# mysz.net
KiCad netlist of a schematic drawn in EAGLE
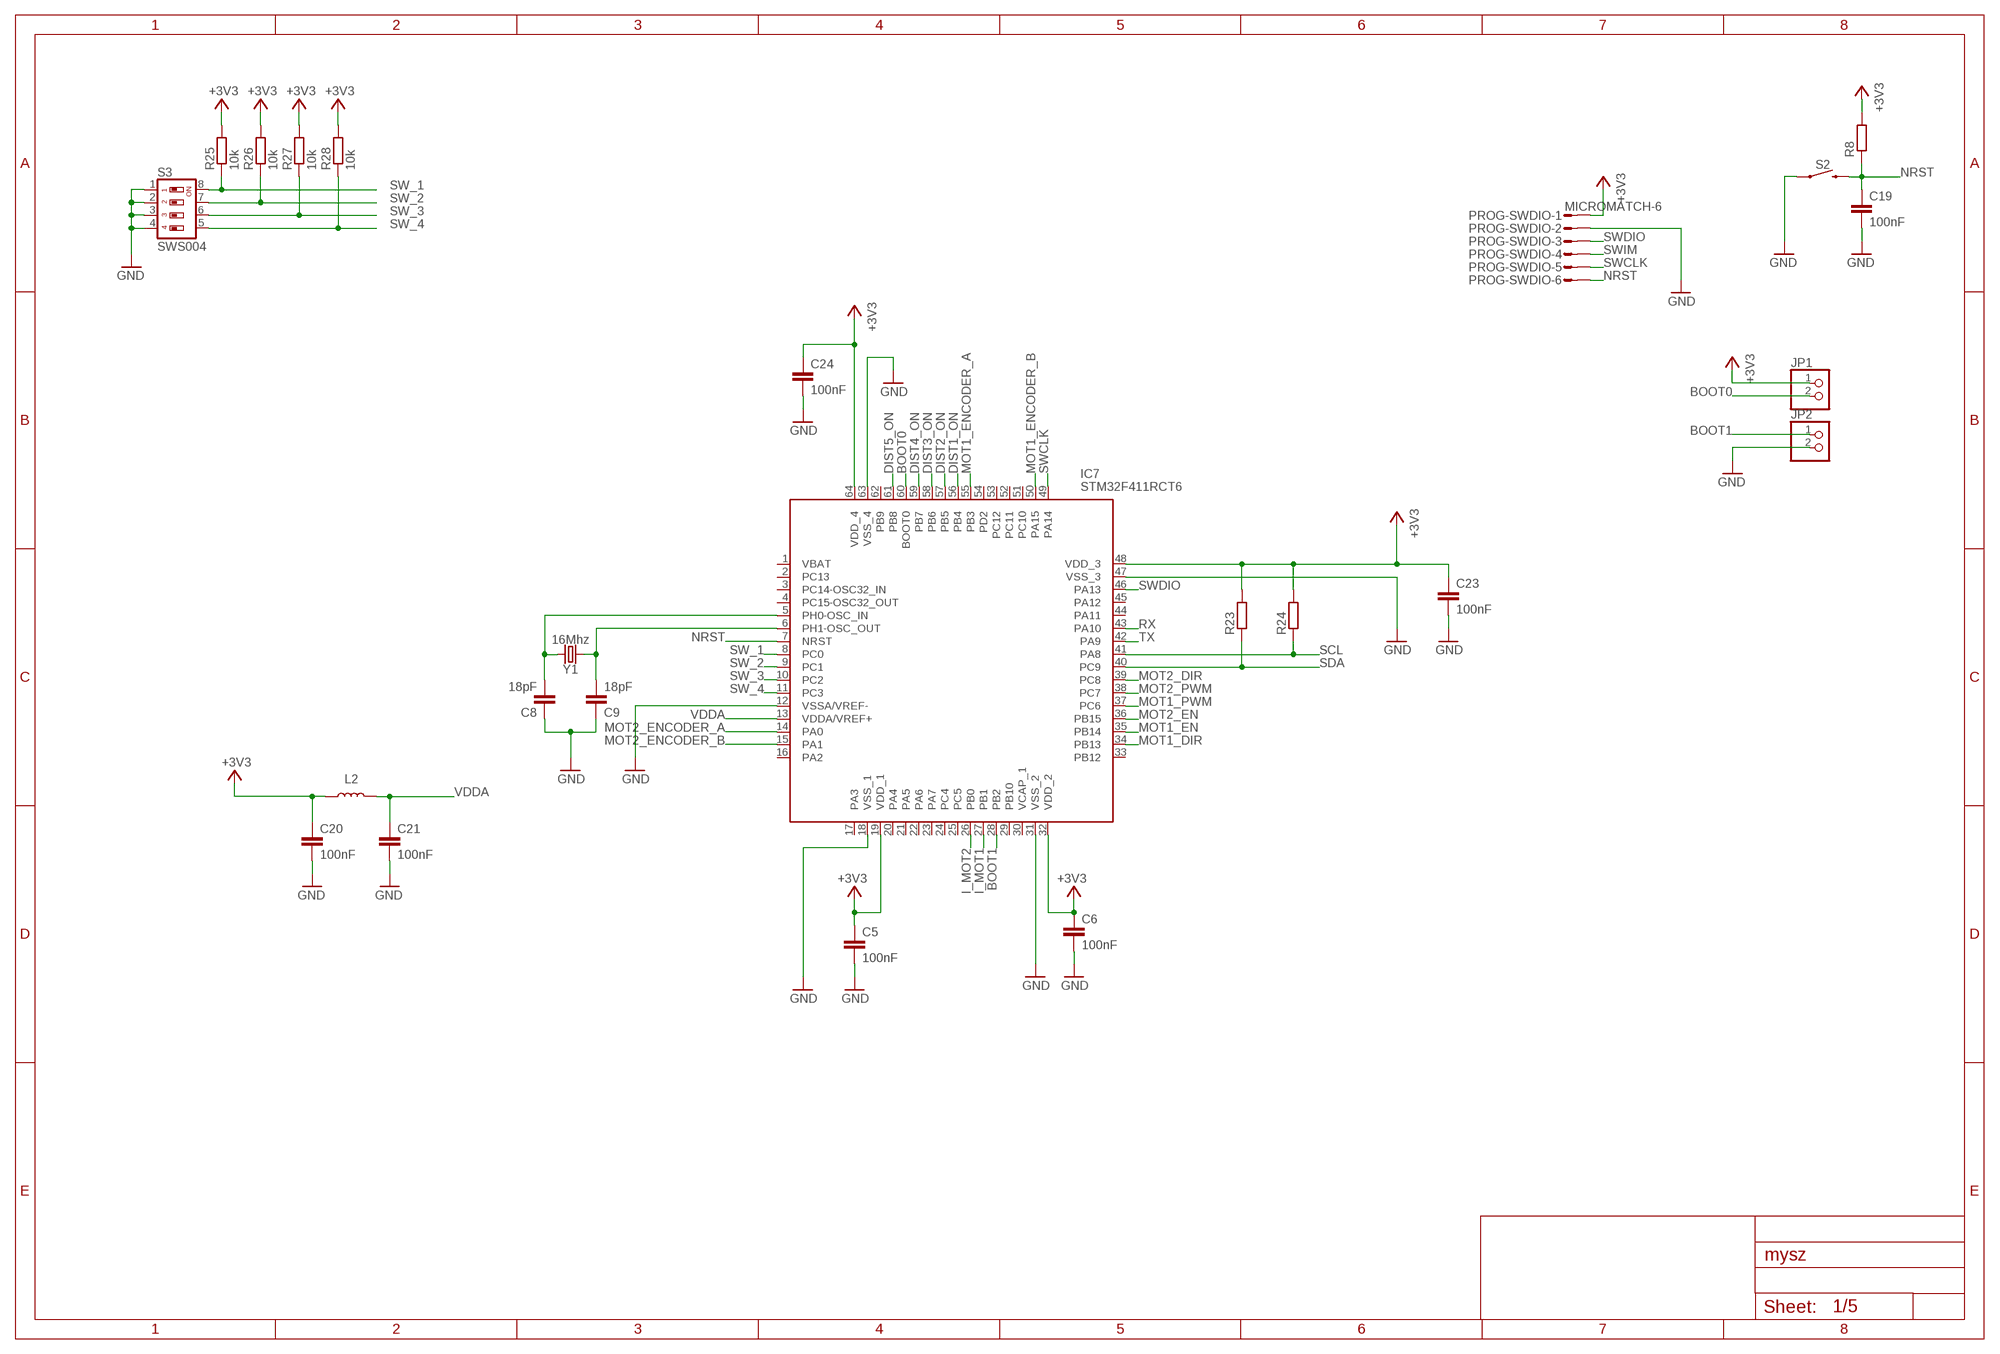
[diagram p0: schematic, sheet 1]
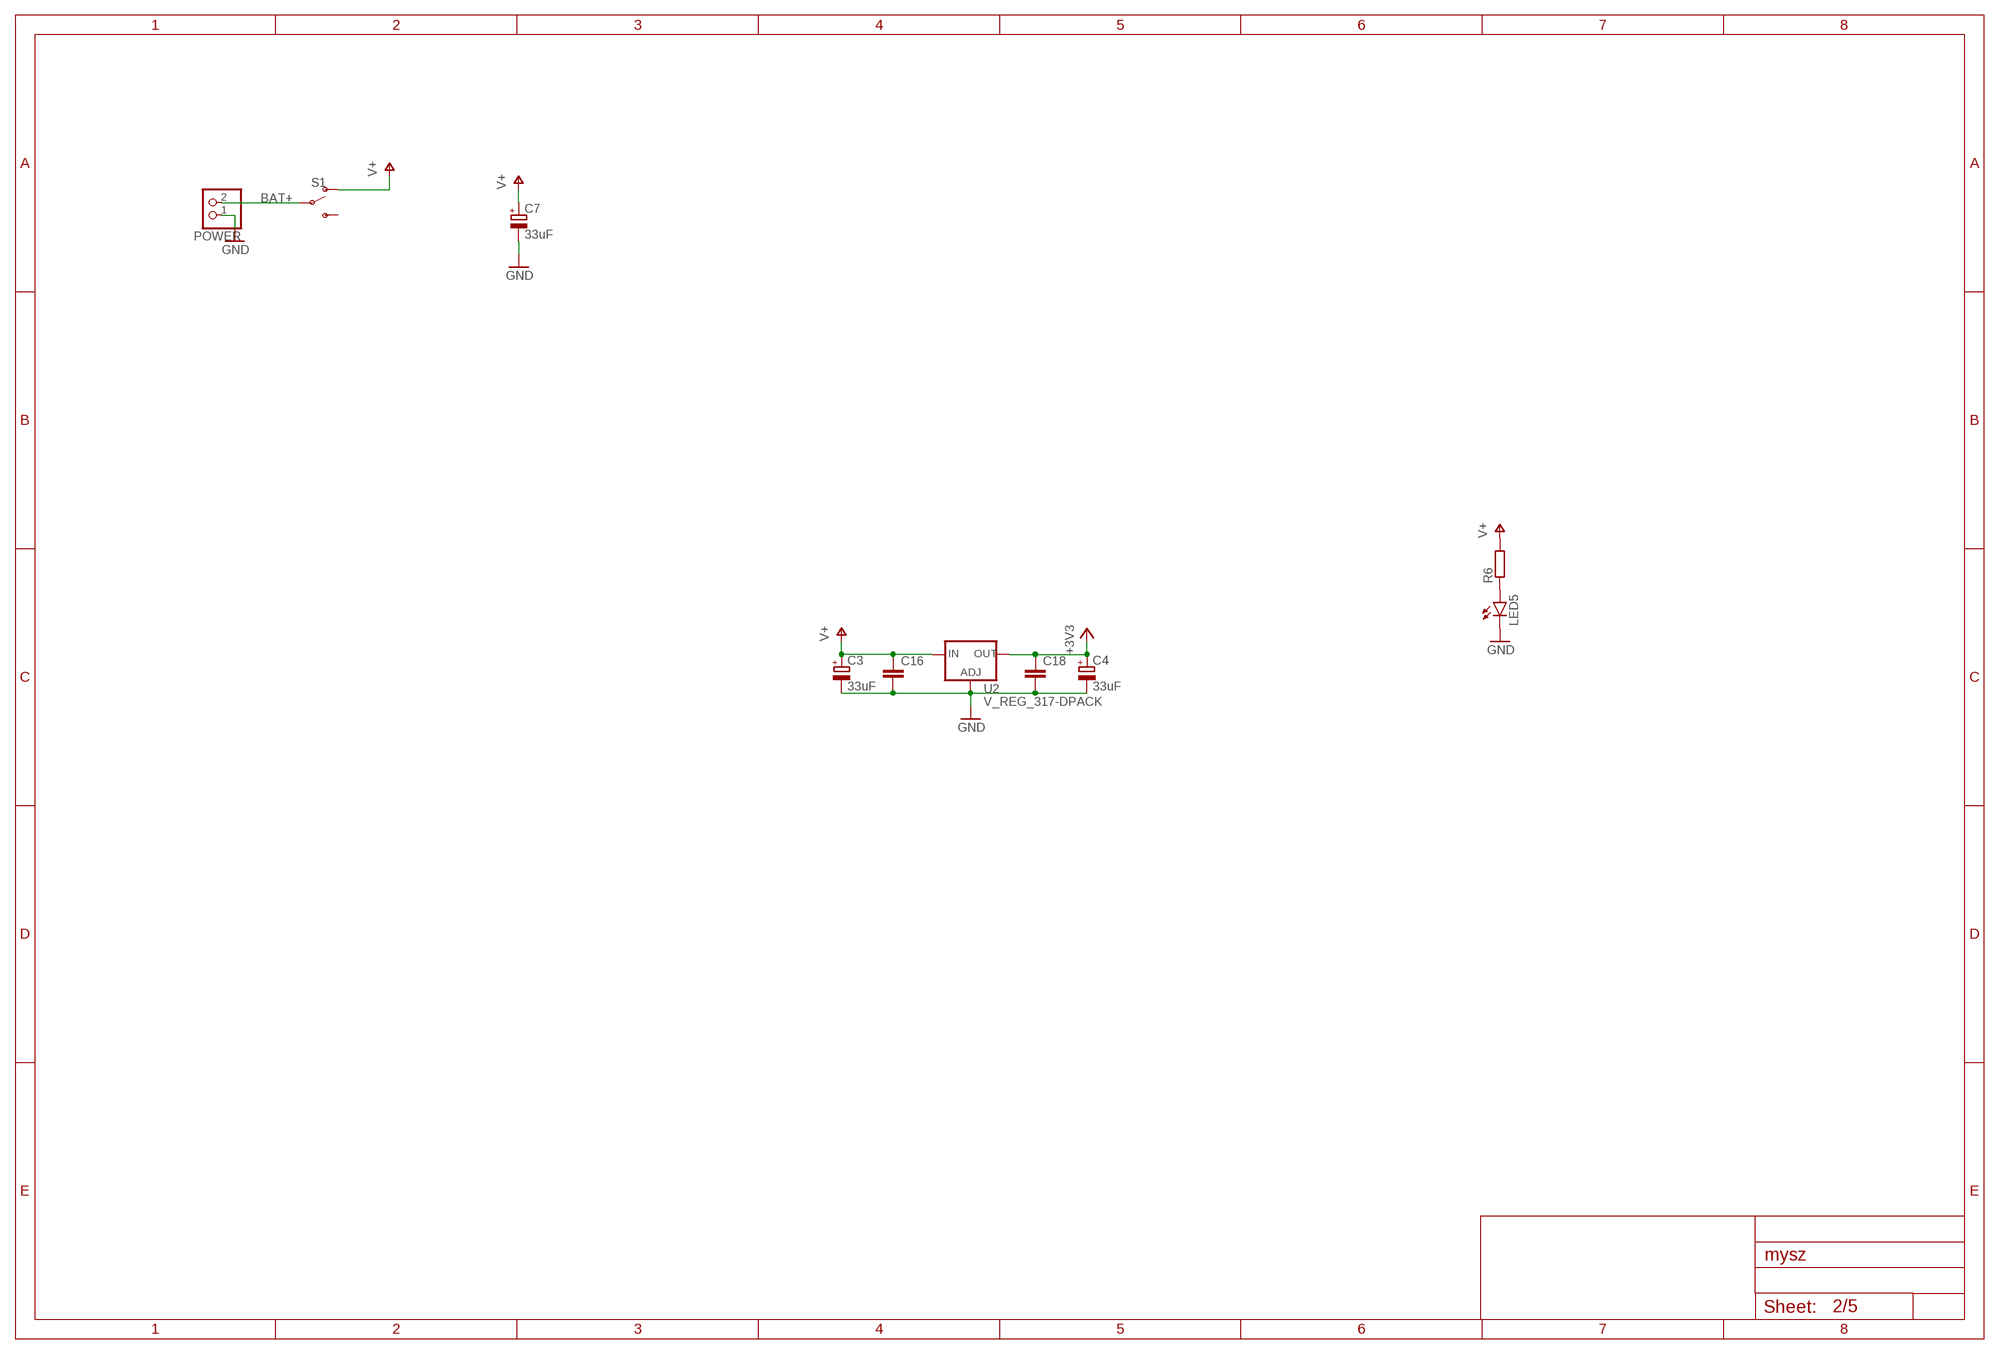
[diagram p1: schematic, sheet 2]
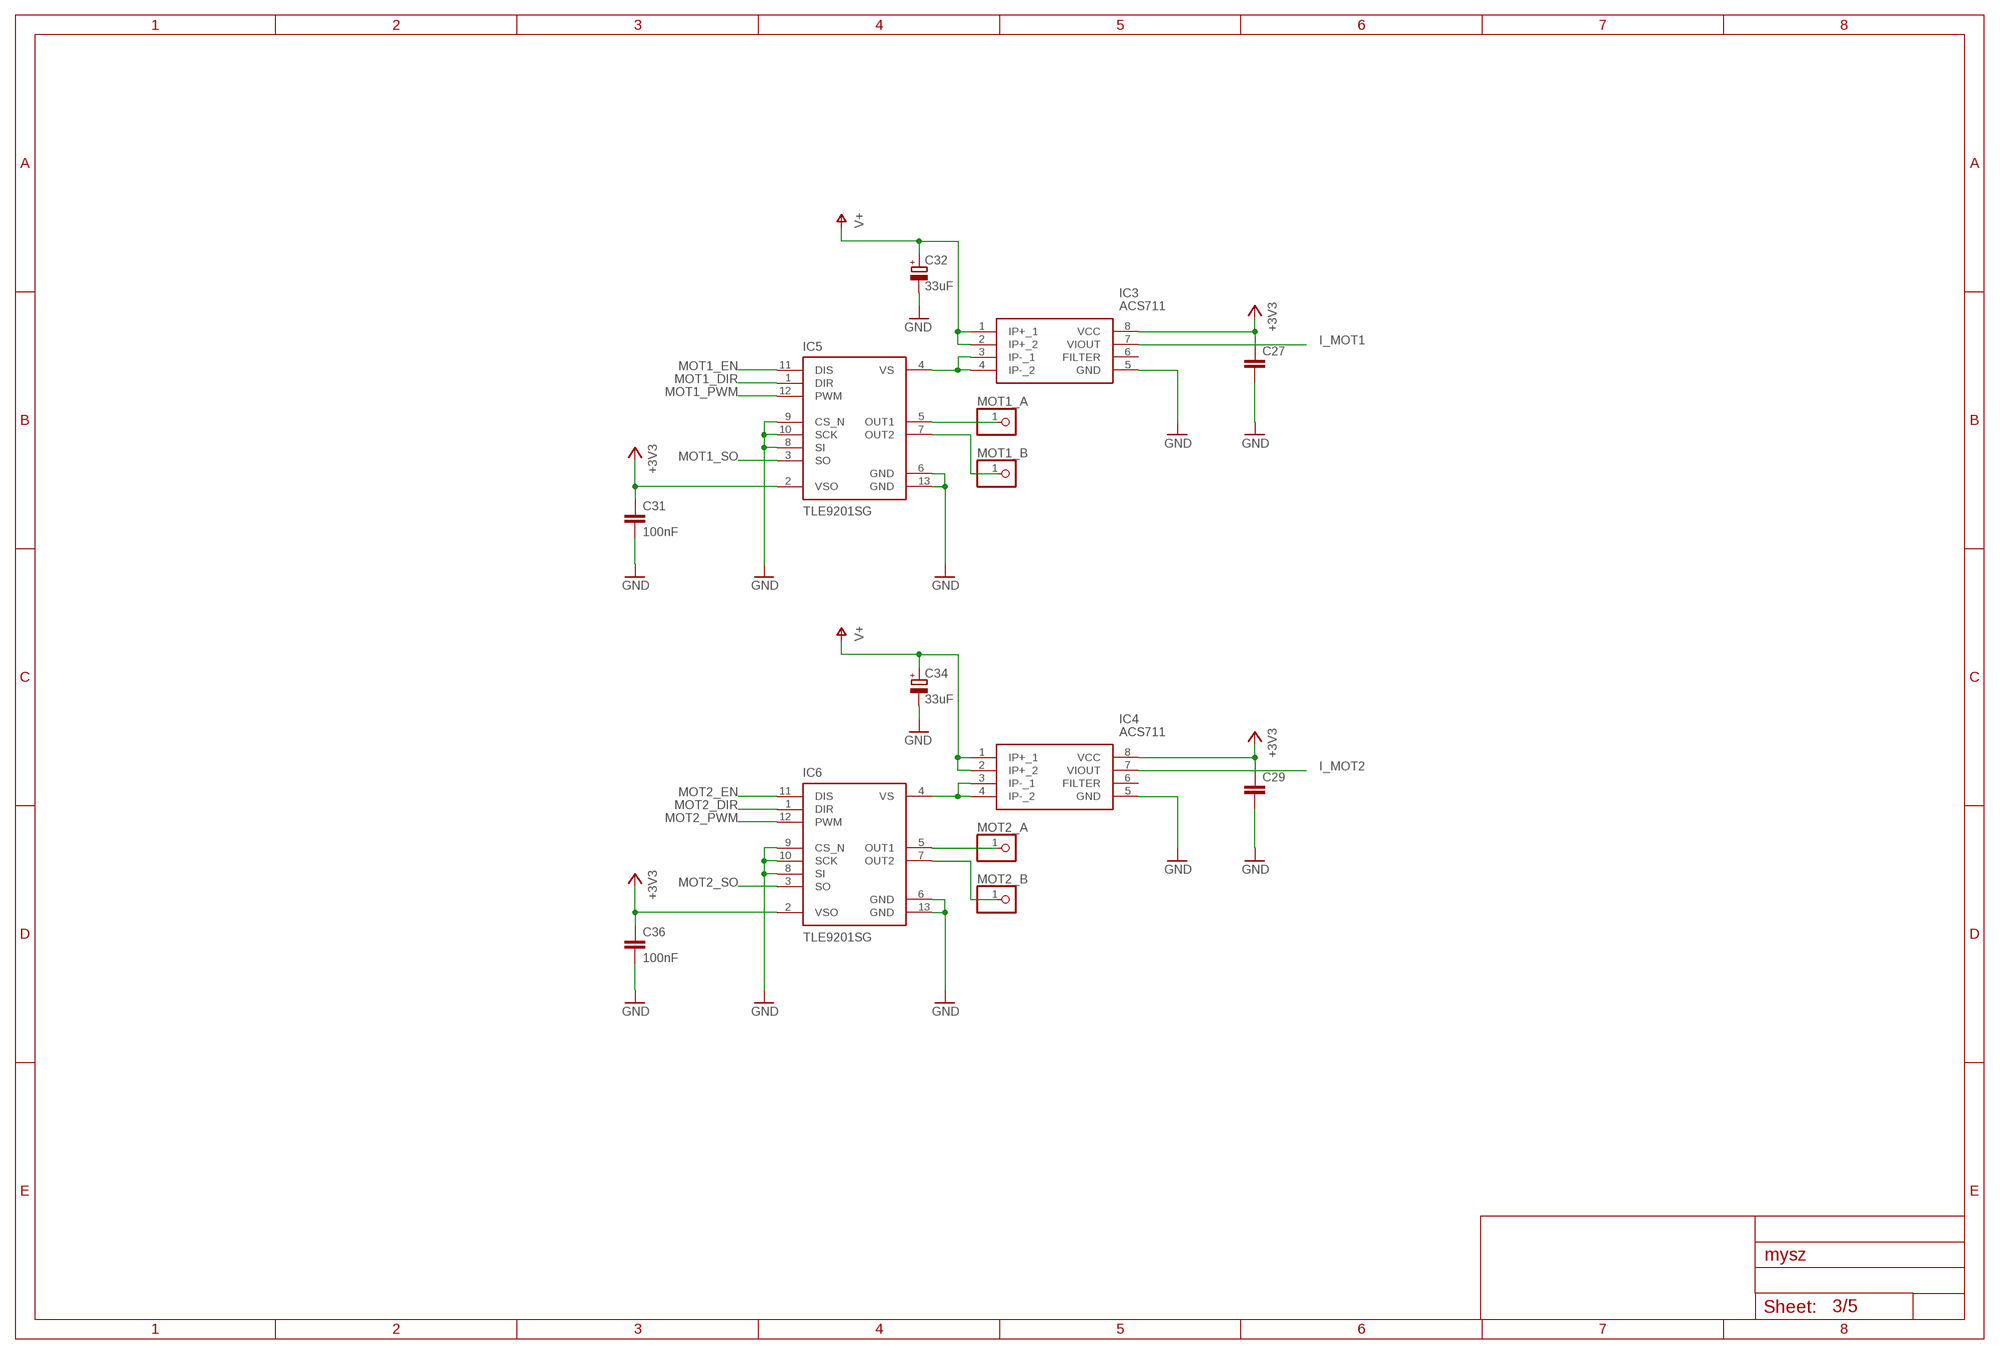
[diagram p2: schematic, sheet 3]
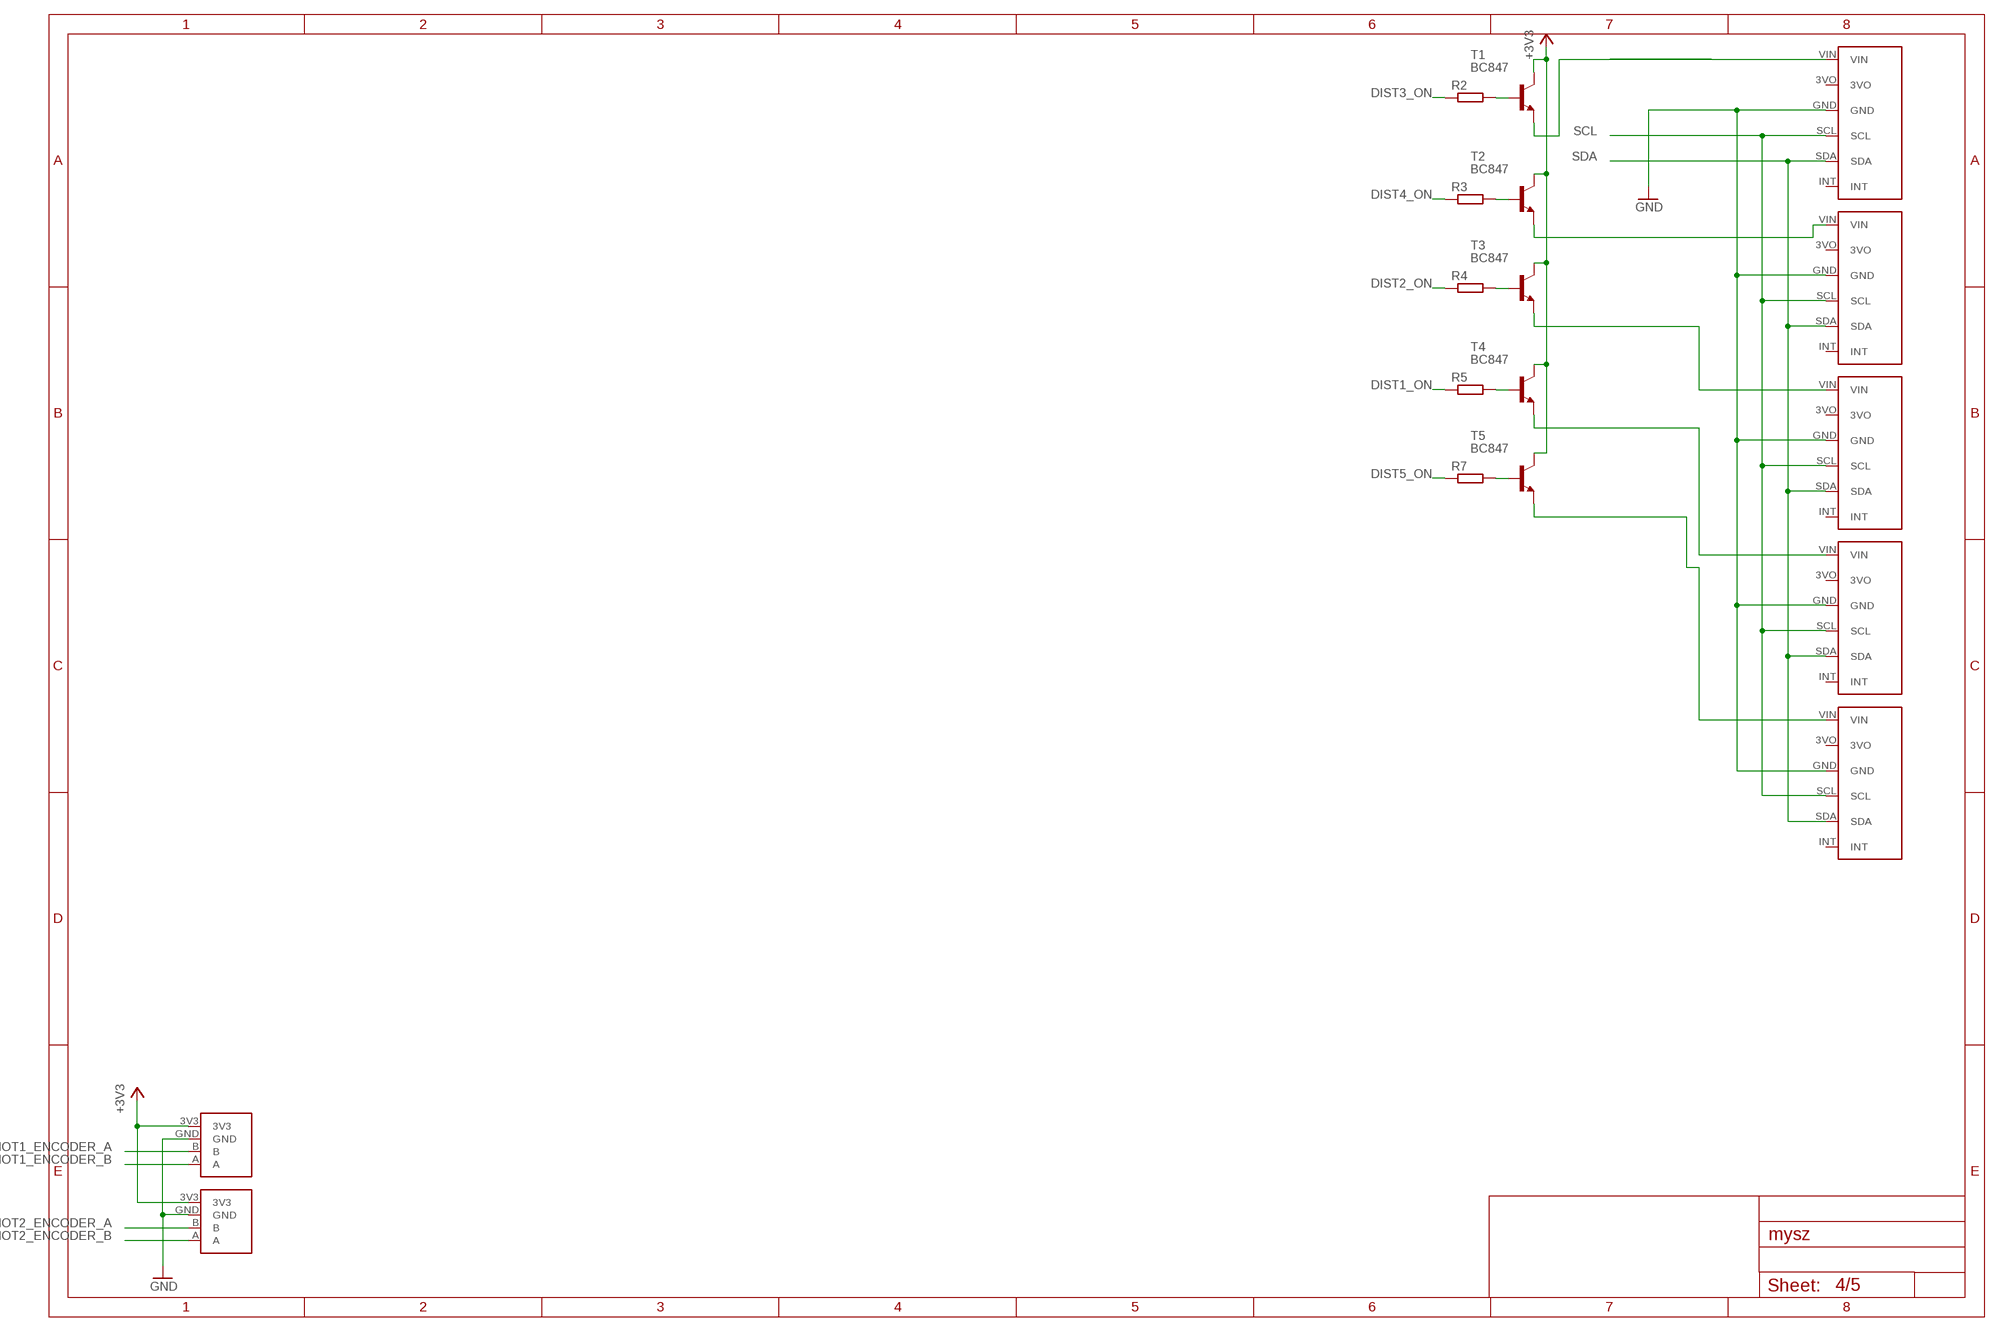
[diagram p3: schematic, sheet 4]
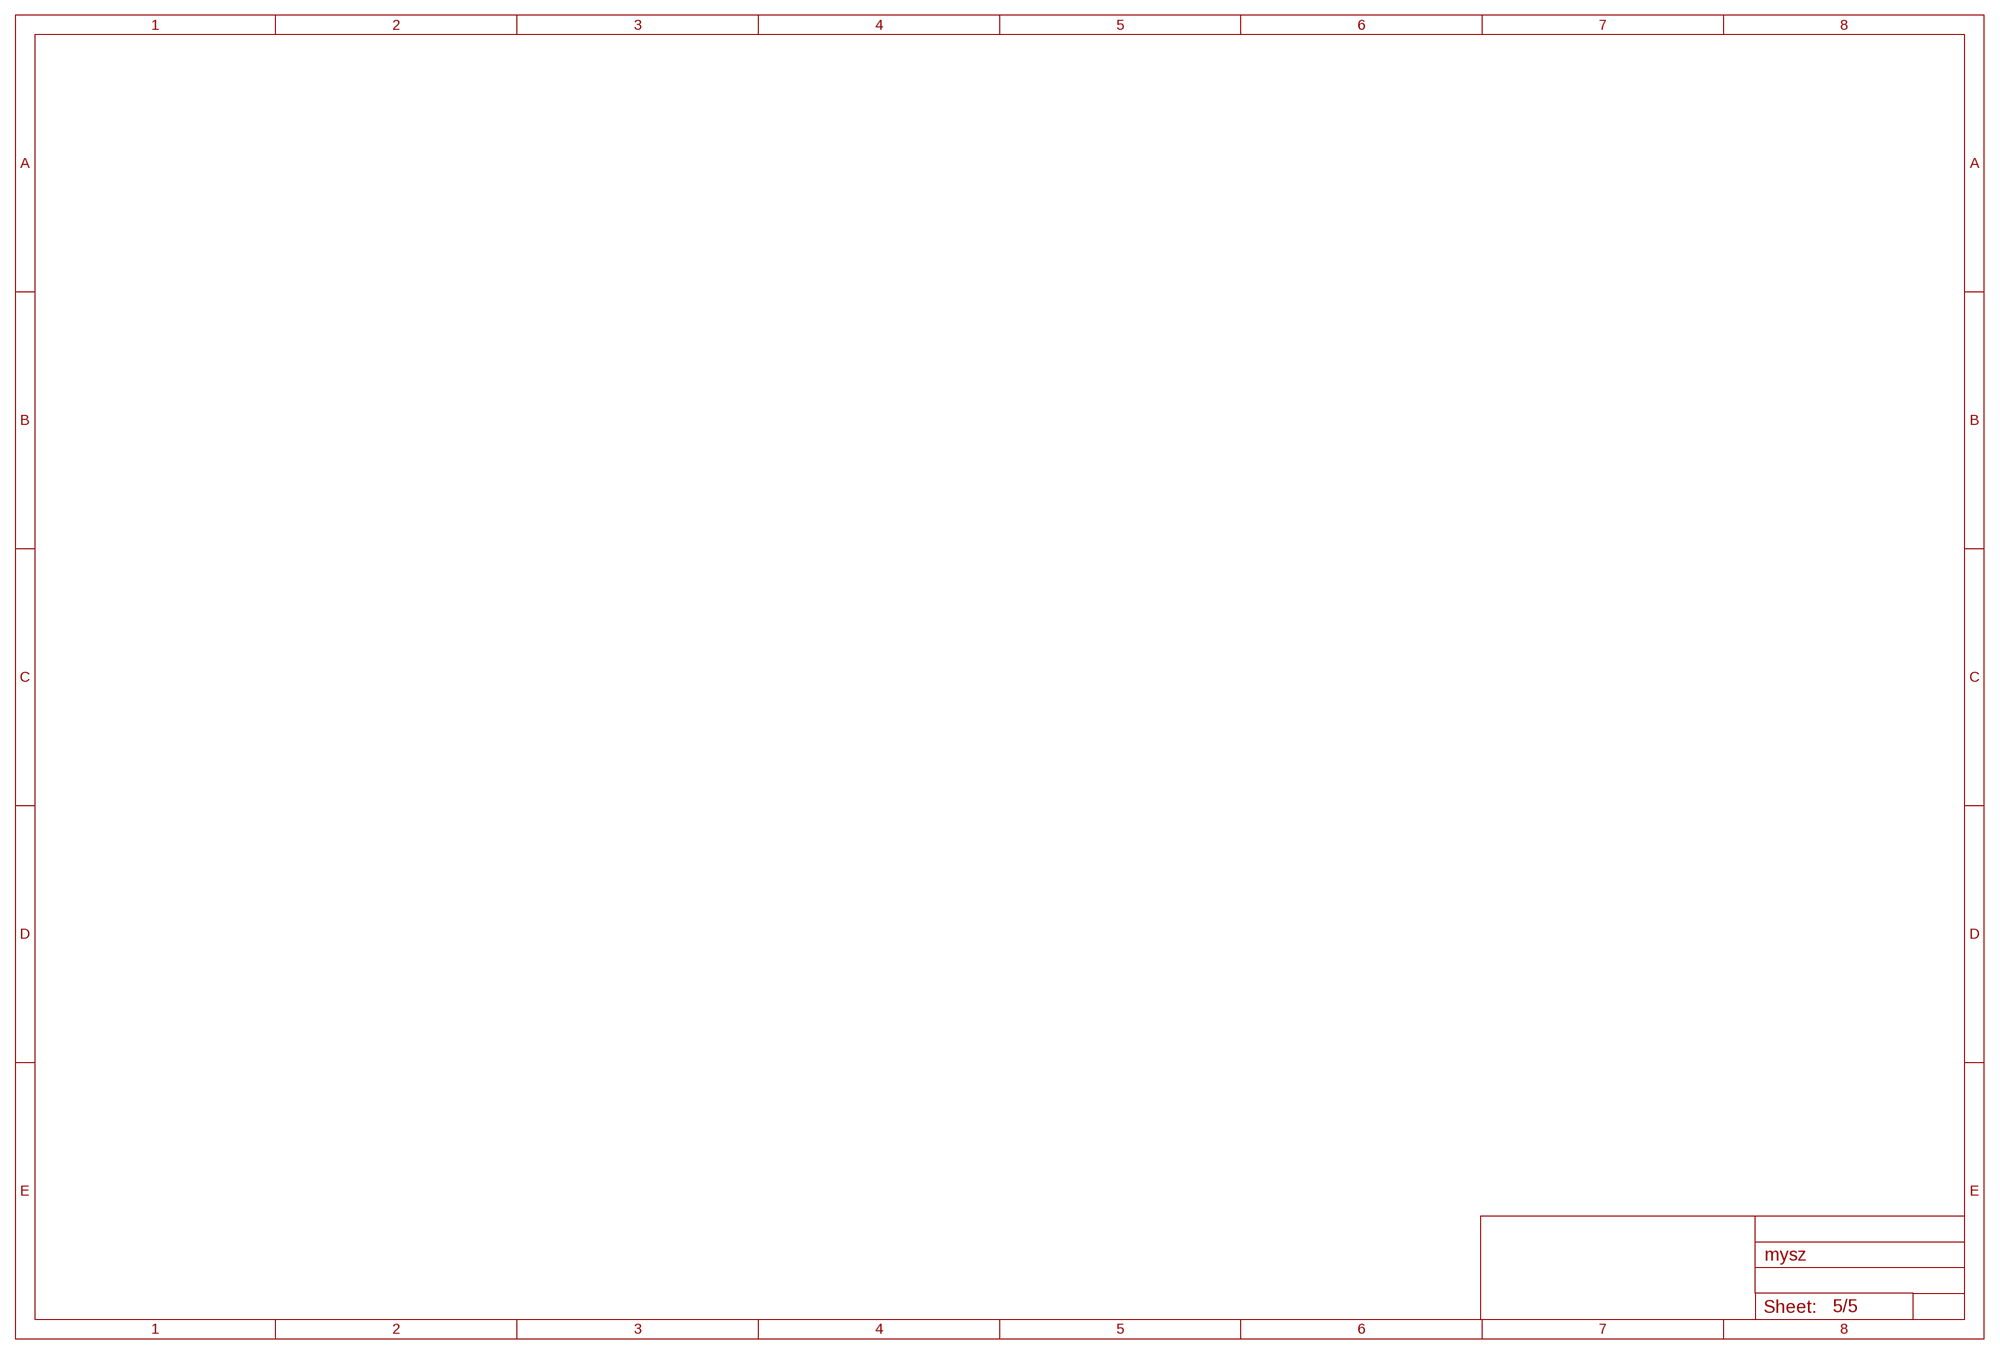
[diagram p4: schematic, sheet 5]

(export (version "E")
  (design (tool "Eeschema 10.0.6"))
  (components
    (comp (ref "R2")
      (value "RESISTOR_SMD_0603")
      (footprint "eagle-import:R0603")
      (libsource (lib "eagle-import") (part "RESISTOR_SMD_0603"))
    )
    (comp (ref "R3")
      (value "RESISTOR_SMD_0603")
      (footprint "eagle-import:R0603")
      (libsource (lib "eagle-import") (part "RESISTOR_SMD_0603"))
    )
    (comp (ref "R4")
      (value "RESISTOR_SMD_0603")
      (footprint "eagle-import:R0603")
      (libsource (lib "eagle-import") (part "RESISTOR_SMD_0603"))
    )
    (comp (ref "R5")
      (value "RESISTOR_SMD_0603")
      (footprint "eagle-import:R0603")
      (libsource (lib "eagle-import") (part "RESISTOR_SMD_0603"))
    )
    (comp (ref "R7")
      (value "RESISTOR_SMD_0603")
      (footprint "eagle-import:R0603")
      (libsource (lib "eagle-import") (part "RESISTOR_SMD_0603"))
    )
    (comp (ref "T1")
      (value "BC847")
      (footprint "eagle-import:SOT23")
      (libsource (lib "eagle-import") (part "BC847"))
    )
    (comp (ref "T2")
      (value "BC847")
      (footprint "eagle-import:SOT23")
      (libsource (lib "eagle-import") (part "BC847"))
    )
    (comp (ref "T3")
      (value "BC847")
      (footprint "eagle-import:SOT23")
      (libsource (lib "eagle-import") (part "BC847"))
    )
    (comp (ref "T4")
      (value "BC847")
      (footprint "eagle-import:SOT23")
      (libsource (lib "eagle-import") (part "BC847"))
    )
    (comp (ref "T5")
      (value "BC847")
      (footprint "eagle-import:SOT23")
      (libsource (lib "eagle-import") (part "BC847"))
    )
    (comp (ref "U$7")
      (value "ADAFRUIT-VCNL4010")
      (footprint "eagle-import:ADAFRUIT-VCNL4010")
      (libsource (lib "eagle-import") (part "ADAFRUIT-VCNL4010"))
    )
    (comp (ref "U$8")
      (value "ADAFRUIT-VCNL4010")
      (footprint "eagle-import:ADAFRUIT-VCNL4010")
      (libsource (lib "eagle-import") (part "ADAFRUIT-VCNL4010"))
    )
    (comp (ref "U$9")
      (value "ADAFRUIT-VCNL4010")
      (footprint "eagle-import:ADAFRUIT-VCNL4010")
      (libsource (lib "eagle-import") (part "ADAFRUIT-VCNL4010"))
    )
    (comp (ref "U$10")
      (value "ADAFRUIT-VCNL4010")
      (footprint "eagle-import:ADAFRUIT-VCNL4010")
      (libsource (lib "eagle-import") (part "ADAFRUIT-VCNL4010"))
    )
    (comp (ref "U$11")
      (value "ADAFRUIT-VCNL4010")
      (footprint "eagle-import:ADAFRUIT-VCNL4010")
      (libsource (lib "eagle-import") (part "ADAFRUIT-VCNL4010"))
    )
    (comp (ref "U$13")
      (value "PRIV-AS5040")
      (footprint "eagle-import:PRIV-AS5040")
      (libsource (lib "eagle-import") (part "PRIV-AS5040"))
    )
    (comp (ref "U$14")
      (value "PRIV-AS5040")
      (footprint "eagle-import:PRIV-AS5040")
      (libsource (lib "eagle-import") (part "PRIV-AS5040"))
    )
    (comp (ref "C5")
      (value "100nF")
      (footprint "eagle-import:C0603K")
      (libsource (lib "eagle-import") (part "CAPACITOR_SMD_0603"))
    )
    (comp (ref "C6")
      (value "100nF")
      (footprint "eagle-import:C0603K")
      (libsource (lib "eagle-import") (part "CAPACITOR_SMD_0603"))
    )
    (comp (ref "C8")
      (value "18pF")
      (footprint "eagle-import:C0603K")
      (libsource (lib "eagle-import") (part "CAPACITOR_SMD_0603"))
    )
    (comp (ref "C9")
      (value "18pF")
      (footprint "eagle-import:C0603K")
      (libsource (lib "eagle-import") (part "CAPACITOR_SMD_0603"))
    )
    (comp (ref "C19")
      (value "100nF")
      (footprint "eagle-import:C0603K")
      (libsource (lib "eagle-import") (part "CAPACITOR_SMD_0603"))
    )
    (comp (ref "C20")
      (value "100nF")
      (footprint "eagle-import:C0603K")
      (libsource (lib "eagle-import") (part "CAPACITOR_SMD_0603"))
    )
    (comp (ref "C21")
      (value "100nF")
      (footprint "eagle-import:C0603K")
      (libsource (lib "eagle-import") (part "CAPACITOR_SMD_0603"))
    )
    (comp (ref "C23")
      (value "100nF")
      (footprint "eagle-import:C0603K")
      (libsource (lib "eagle-import") (part "CAPACITOR_SMD_0603"))
    )
    (comp (ref "C24")
      (value "100nF")
      (footprint "eagle-import:C0603K")
      (libsource (lib "eagle-import") (part "CAPACITOR_SMD_0603"))
    )
    (comp (ref "IC7")
      (value "STM32F411RCT6")
      (footprint "eagle-import:QFP50P1200X1200X160-64N")
      (libsource (lib "eagle-import") (part "STM32F411RCT6"))
    )
    (comp (ref "JP1")
      (value "PINHD-1X2")
      (footprint "eagle-import:1X02")
      (libsource (lib "eagle-import") (part "PINHD-1X2"))
    )
    (comp (ref "JP2")
      (value "PINHD-1X2")
      (footprint "eagle-import:1X02")
      (libsource (lib "eagle-import") (part "PINHD-1X2"))
    )
    (comp (ref "L2")
      (value "INDUCTOR-0603")
      (footprint "eagle-import:R0603")
      (libsource (lib "eagle-import") (part "INDUCTOR-0603"))
    )
    (comp (ref "PROG-SWDIO")
      (value "MICROMATCH-6")
      (footprint "eagle-import:MICROMATCH-6")
      (fields (field (name "MPN") "7-215464-6"))
      (libsource (lib "eagle-import") (part "MICROMATCH-6"))
    )
    (comp (ref "R8")
      (value "RESISTOR_SMD_0603")
      (footprint "eagle-import:R0603")
      (libsource (lib "eagle-import") (part "RESISTOR_SMD_0603"))
    )
    (comp (ref "R23")
      (value "RESISTOR_SMD_0603")
      (footprint "eagle-import:R0603")
      (libsource (lib "eagle-import") (part "RESISTOR_SMD_0603"))
    )
    (comp (ref "R24")
      (value "RESISTOR_SMD_0603")
      (footprint "eagle-import:R0603")
      (libsource (lib "eagle-import") (part "RESISTOR_SMD_0603"))
    )
    (comp (ref "R25")
      (value "10k")
      (footprint "eagle-import:R0603")
      (libsource (lib "eagle-import") (part "RESISTOR_SMD_0603"))
    )
    (comp (ref "R26")
      (value "10k")
      (footprint "eagle-import:R0603")
      (libsource (lib "eagle-import") (part "RESISTOR_SMD_0603"))
    )
    (comp (ref "R27")
      (value "10k")
      (footprint "eagle-import:R0603")
      (libsource (lib "eagle-import") (part "RESISTOR_SMD_0603"))
    )
    (comp (ref "R28")
      (value "10k")
      (footprint "eagle-import:R0603")
      (libsource (lib "eagle-import") (part "RESISTOR_SMD_0603"))
    )
    (comp (ref "S2")
      (value "MOMENTARY-SWITCH-SPST-SMD-6.2MM_TALL")
      (footprint "eagle-import:TACTILE_SWITCH_SMD_6.2MM_TALL")
      (libsource (lib "eagle-import") (part "MOMENTARY-SWITCH-SPST-SMD-6.2MM_TALL"))
    )
    (comp (ref "S3")
      (value "SWS004")
      (footprint "eagle-import:SMS-004")
      (libsource (lib "eagle-import") (part "SWS004"))
    )
    (comp (ref "Y1")
      (value "16Mhz")
      (footprint "eagle-import:CRYSTAL-SMD-5X3.2-4PAD")
      (libsource (lib "eagle-import") (part "CRYSTAL_SMALL{dblquote}"))
    )
    (comp (ref "C3")
      (value "33uF")
      (footprint "eagle-import:PANASONIC_C")
      (libsource (lib "eagle-import") (part "CPOL-EUC"))
    )
    (comp (ref "C4")
      (value "33uF")
      (footprint "eagle-import:PANASONIC_C")
      (libsource (lib "eagle-import") (part "CPOL-EUC"))
    )
    (comp (ref "C7")
      (value "33uF")
      (footprint "eagle-import:PANASONIC_C")
      (libsource (lib "eagle-import") (part "CPOL-EUC"))
    )
    (comp (ref "C16")
      (value "CAPACITOR_SMD_0603")
      (footprint "eagle-import:C0603K")
      (libsource (lib "eagle-import") (part "CAPACITOR_SMD_0603"))
    )
    (comp (ref "C18")
      (value "CAPACITOR_SMD_0603")
      (footprint "eagle-import:C0603K")
      (libsource (lib "eagle-import") (part "CAPACITOR_SMD_0603"))
    )
    (comp (ref "LED5")
      (value "LEDCHIPLED_0603")
      (footprint "eagle-import:CHIPLED_0603")
      (libsource (lib "eagle-import") (part "LEDCHIPLED_0603"))
    )
    (comp (ref "POWER")
      (value "PINHD-1X2")
      (footprint "eagle-import:1X02")
      (libsource (lib "eagle-import") (part "PINHD-1X2"))
    )
    (comp (ref "R6")
      (value "RESISTOR_SMD_0603")
      (footprint "eagle-import:R0603")
      (libsource (lib "eagle-import") (part "RESISTOR_SMD_0603"))
    )
    (comp (ref "S1")
      (value "SWITCH-SPDT-PTH-11.6X4.0MM")
      (footprint "eagle-import:SWITCH_SPDT_PTH_11.6X4.0MM")
      (libsource (lib "eagle-import") (part "SWITCH-SPDT-PTH-11.6X4.0MM"))
    )
    (comp (ref "U2")
      (value "V_REG_317-DPACK")
      (footprint "eagle-import:V-REG_DPACK")
      (libsource (lib "eagle-import") (part "V_REG_317-DPACK"))
    )
    (comp (ref "C27")
      (value "CAPACITOR_SMD_0603")
      (footprint "eagle-import:C0603K")
      (libsource (lib "eagle-import") (part "CAPACITOR_SMD_0603"))
    )
    (comp (ref "C29")
      (value "CAPACITOR_SMD_0603")
      (footprint "eagle-import:C0603K")
      (libsource (lib "eagle-import") (part "CAPACITOR_SMD_0603"))
    )
    (comp (ref "C31")
      (value "100nF")
      (footprint "eagle-import:C0603K")
      (libsource (lib "eagle-import") (part "CAPACITOR_SMD_0603"))
    )
    (comp (ref "C32")
      (value "33uF")
      (footprint "eagle-import:PANASONIC_C")
      (libsource (lib "eagle-import") (part "CPOL-EUC"))
    )
    (comp (ref "C34")
      (value "33uF")
      (footprint "eagle-import:PANASONIC_C")
      (libsource (lib "eagle-import") (part "CPOL-EUC"))
    )
    (comp (ref "C36")
      (value "100nF")
      (footprint "eagle-import:C0603K")
      (libsource (lib "eagle-import") (part "CAPACITOR_SMD_0603"))
    )
    (comp (ref "IC3")
      (value "ACS711")
      (footprint "eagle-import:SOIC127P600X175-8N")
      (fields (field (name "ARROW_PART_NUMBER") "ACS712"))
      (libsource (lib "eagle-import") (part "ACS712"))
    )
    (comp (ref "IC4")
      (value "ACS711")
      (footprint "eagle-import:SOIC127P600X175-8N")
      (fields (field (name "ARROW_PART_NUMBER") "ACS712"))
      (libsource (lib "eagle-import") (part "ACS712"))
    )
    (comp (ref "IC5")
      (value "TLE9201SG")
      (footprint "eagle-import:PG-DSO-12-9")
      (fields (field (name "RS_PART_NUMBER") "1661194"))
      (libsource (lib "eagle-import") (part "TLE9201SG"))
    )
    (comp (ref "IC6")
      (value "TLE9201SG")
      (footprint "eagle-import:PG-DSO-12-9")
      (fields (field (name "RS_PART_NUMBER") "1661194"))
      (libsource (lib "eagle-import") (part "TLE9201SG"))
    )
    (comp (ref "MOT1_A")
      (value "PINHD-1X1")
      (footprint "eagle-import:1X01")
      (libsource (lib "eagle-import") (part "PINHD-1X1"))
    )
    (comp (ref "MOT1_B")
      (value "PINHD-1X1")
      (footprint "eagle-import:1X01")
      (libsource (lib "eagle-import") (part "PINHD-1X1"))
    )
    (comp (ref "MOT2_A")
      (value "PINHD-1X1")
      (footprint "eagle-import:1X01")
      (libsource (lib "eagle-import") (part "PINHD-1X1"))
    )
    (comp (ref "MOT2_B")
      (value "PINHD-1X1")
      (footprint "eagle-import:1X01")
      (libsource (lib "eagle-import") (part "PINHD-1X1"))
    )
  )
  (nets
    (net (code "1") (name "+3V3") (class "Default")
      (node (ref "C18") (pin "1") (pinfunction "1_1") (pintype "passive"))
      (node (ref "C20") (pin "1") (pinfunction "1_1") (pintype "passive"))
      (node (ref "C23") (pin "1") (pinfunction "1_1") (pintype "passive"))
      (node (ref "C24") (pin "1") (pinfunction "1_1") (pintype "passive"))
      (node (ref "C27") (pin "1") (pinfunction "1_1") (pintype "passive"))
      (node (ref "C29") (pin "1") (pinfunction "1_1") (pintype "passive"))
      (node (ref "C31") (pin "1") (pinfunction "1_1") (pintype "passive"))
      (node (ref "C36") (pin "1") (pinfunction "1_1") (pintype "passive"))
      (node (ref "C4") (pin "+") (pinfunction "+_+") (pintype "passive"))
      (node (ref "C5") (pin "1") (pinfunction "1_1") (pintype "passive"))
      (node (ref "C6") (pin "1") (pinfunction "1_1") (pintype "passive"))
      (node (ref "IC3") (pin "8") (pinfunction "VCC_8") (pintype "bidirectional"))
      (node (ref "IC4") (pin "8") (pinfunction "VCC_8") (pintype "bidirectional"))
      (node (ref "IC5") (pin "2") (pinfunction "VSO_2") (pintype "input"))
      (node (ref "IC6") (pin "2") (pinfunction "VSO_2") (pintype "input"))
      (node (ref "IC7") (pin "19") (pinfunction "VDD_1_19") (pintype "bidirectional"))
      (node (ref "IC7") (pin "32") (pinfunction "VDD_2_32") (pintype "bidirectional"))
      (node (ref "IC7") (pin "48") (pinfunction "VDD_3_48") (pintype "bidirectional"))
      (node (ref "IC7") (pin "64") (pinfunction "VDD_4_64") (pintype "bidirectional"))
      (node (ref "JP1") (pin "1") (pinfunction "1_1") (pintype "passive"))
      (node (ref "L2") (pin "1") (pinfunction "1_1") (pintype "passive"))
      (node (ref "PROG-SWDIO") (pin "1") (pinfunction "S_1") (pintype "passive"))
      (node (ref "R23") (pin "2") (pinfunction "2_2") (pintype "passive"))
      (node (ref "R24") (pin "2") (pinfunction "2_2") (pintype "passive"))
      (node (ref "R25") (pin "2") (pinfunction "2_2") (pintype "passive"))
      (node (ref "R26") (pin "2") (pinfunction "2_2") (pintype "passive"))
      (node (ref "R27") (pin "2") (pinfunction "2_2") (pintype "passive"))
      (node (ref "R28") (pin "2") (pinfunction "2_2") (pintype "passive"))
      (node (ref "R8") (pin "2") (pinfunction "2_2") (pintype "passive"))
      (node (ref "T1") (pin "3") (pinfunction "C_3") (pintype "passive"))
      (node (ref "T2") (pin "3") (pinfunction "C_3") (pintype "passive"))
      (node (ref "T3") (pin "3") (pinfunction "C_3") (pintype "passive"))
      (node (ref "T4") (pin "3") (pinfunction "C_3") (pintype "passive"))
      (node (ref "T5") (pin "3") (pinfunction "C_3") (pintype "passive"))
      (node (ref "U$13") (pin "3V3") (pinfunction "3V3_3V3") (pintype "bidirectional"))
      (node (ref "U$14") (pin "3V3") (pinfunction "3V3_3V3") (pintype "bidirectional"))
      (node (ref "U2") (pin "4") (pinfunction "OUT_4") (pintype "output"))
    )
    (net (code "2") (name "BAT+") (class "Default")
      (node (ref "POWER") (pin "2") (pinfunction "2_2") (pintype "passive"))
      (node (ref "S1") (pin "2") (pinfunction "P_2") (pintype "passive"))
    )
    (net (code "3") (name "BOOT0") (class "Default")
      (node (ref "IC7") (pin "60") (pinfunction "BOOT0_60") (pintype "bidirectional"))
      (node (ref "JP1") (pin "2") (pinfunction "2_2") (pintype "passive"))
    )
    (net (code "4") (name "BOOT1") (class "Default")
      (node (ref "IC7") (pin "28") (pinfunction "PB2_28") (pintype "bidirectional"))
      (node (ref "JP2") (pin "1") (pinfunction "1_1") (pintype "passive"))
    )
    (net (code "5") (name "DIST1_ON") (class "Default")
      (node (ref "IC7") (pin "56") (pinfunction "PB4_56") (pintype "bidirectional"))
      (node (ref "R5") (pin "1") (pinfunction "1_1") (pintype "passive"))
    )
    (net (code "6") (name "DIST2_ON") (class "Default")
      (node (ref "IC7") (pin "57") (pinfunction "PB5_57") (pintype "bidirectional"))
      (node (ref "R4") (pin "1") (pinfunction "1_1") (pintype "passive"))
    )
    (net (code "7") (name "DIST3_ON") (class "Default")
      (node (ref "IC7") (pin "58") (pinfunction "PB6_58") (pintype "bidirectional"))
      (node (ref "R2") (pin "1") (pinfunction "1_1") (pintype "passive"))
    )
    (net (code "8") (name "DIST4_ON") (class "Default")
      (node (ref "IC7") (pin "59") (pinfunction "PB7_59") (pintype "bidirectional"))
      (node (ref "R3") (pin "1") (pinfunction "1_1") (pintype "passive"))
    )
    (net (code "9") (name "DIST5_ON") (class "Default")
      (node (ref "IC7") (pin "61") (pinfunction "PB8_61") (pintype "bidirectional"))
      (node (ref "R7") (pin "1") (pinfunction "1_1") (pintype "passive"))
    )
    (net (code "10") (name "GND") (class "Default")
      (node (ref "C16") (pin "2") (pinfunction "2_2") (pintype "passive"))
      (node (ref "C18") (pin "2") (pinfunction "2_2") (pintype "passive"))
      (node (ref "C19") (pin "2") (pinfunction "2_2") (pintype "passive"))
      (node (ref "C20") (pin "2") (pinfunction "2_2") (pintype "passive"))
      (node (ref "C21") (pin "2") (pinfunction "2_2") (pintype "passive"))
      (node (ref "C23") (pin "2") (pinfunction "2_2") (pintype "passive"))
      (node (ref "C24") (pin "2") (pinfunction "2_2") (pintype "passive"))
      (node (ref "C27") (pin "2") (pinfunction "2_2") (pintype "passive"))
      (node (ref "C29") (pin "2") (pinfunction "2_2") (pintype "passive"))
      (node (ref "C3") (pin "-") (pinfunction "-_-") (pintype "passive"))
      (node (ref "C31") (pin "2") (pinfunction "2_2") (pintype "passive"))
      (node (ref "C32") (pin "-") (pinfunction "-_-") (pintype "passive"))
      (node (ref "C34") (pin "-") (pinfunction "-_-") (pintype "passive"))
      (node (ref "C36") (pin "2") (pinfunction "2_2") (pintype "passive"))
      (node (ref "C4") (pin "-") (pinfunction "-_-") (pintype "passive"))
      (node (ref "C5") (pin "2") (pinfunction "2_2") (pintype "passive"))
      (node (ref "C6") (pin "2") (pinfunction "2_2") (pintype "passive"))
      (node (ref "C7") (pin "-") (pinfunction "-_-") (pintype "passive"))
      (node (ref "C8") (pin "1") (pinfunction "1_1") (pintype "passive"))
      (node (ref "C9") (pin "1") (pinfunction "1_1") (pintype "passive"))
      (node (ref "IC3") (pin "5") (pinfunction "GND_5") (pintype "bidirectional"))
      (node (ref "IC4") (pin "5") (pinfunction "GND_5") (pintype "bidirectional"))
      (node (ref "IC5") (pin "10") (pinfunction "SCK_10") (pintype "input"))
      (node (ref "IC5") (pin "13") (pinfunction "GND_13") (pintype "power_in"))
      (node (ref "IC5") (pin "6") (pinfunction "GND_6") (pintype "power_in"))
      (node (ref "IC5") (pin "8") (pinfunction "SI_8") (pintype "input"))
      (node (ref "IC5") (pin "9") (pinfunction "CS_N_9") (pintype "input"))
      (node (ref "IC6") (pin "10") (pinfunction "SCK_10") (pintype "input"))
      (node (ref "IC6") (pin "13") (pinfunction "GND_13") (pintype "power_in"))
      (node (ref "IC6") (pin "6") (pinfunction "GND_6") (pintype "power_in"))
      (node (ref "IC6") (pin "8") (pinfunction "SI_8") (pintype "input"))
      (node (ref "IC6") (pin "9") (pinfunction "CS_N_9") (pintype "input"))
      (node (ref "IC7") (pin "12") (pinfunction "VSSA/VREF-_12") (pintype "bidirectional"))
      (node (ref "IC7") (pin "18") (pinfunction "VSS_1_18") (pintype "bidirectional"))
      (node (ref "IC7") (pin "31") (pinfunction "VSS_2_31") (pintype "bidirectional"))
      (node (ref "IC7") (pin "47") (pinfunction "VSS_3_47") (pintype "bidirectional"))
      (node (ref "IC7") (pin "63") (pinfunction "VSS_4_63") (pintype "bidirectional"))
      (node (ref "JP2") (pin "2") (pinfunction "2_2") (pintype "passive"))
      (node (ref "LED5") (pin "C") (pinfunction "C_C") (pintype "passive"))
      (node (ref "POWER") (pin "1") (pinfunction "1_1") (pintype "passive"))
      (node (ref "PROG-SWDIO") (pin "2") (pinfunction "S_2") (pintype "passive"))
      (node (ref "S2") (pin "A1") (pinfunction "1_A1") (pintype "passive"))
      (node (ref "S2") (pin "A2") (pinfunction "1_A2") (pintype "passive"))
      (node (ref "S3") (pin "1") (pinfunction "1_1") (pintype "passive"))
      (node (ref "S3") (pin "2") (pinfunction "2_2") (pintype "passive"))
      (node (ref "S3") (pin "3") (pinfunction "3_3") (pintype "passive"))
      (node (ref "S3") (pin "4") (pinfunction "4_4") (pintype "passive"))
      (node (ref "U$10") (pin "GND") (pinfunction "GND_GND") (pintype "bidirectional"))
      (node (ref "U$11") (pin "GND") (pinfunction "GND_GND") (pintype "bidirectional"))
      (node (ref "U$13") (pin "GND") (pinfunction "GND_GND") (pintype "bidirectional"))
      (node (ref "U$14") (pin "GND") (pinfunction "GND_GND") (pintype "bidirectional"))
      (node (ref "U$7") (pin "GND") (pinfunction "GND_GND") (pintype "bidirectional"))
      (node (ref "U$8") (pin "GND") (pinfunction "GND_GND") (pintype "bidirectional"))
      (node (ref "U$9") (pin "GND") (pinfunction "GND_GND") (pintype "bidirectional"))
      (node (ref "U2") (pin "1") (pinfunction "ADJ_1") (pintype "input"))
    )
    (net (code "11") (name "I_MOT1") (class "Default")
      (node (ref "IC3") (pin "7") (pinfunction "VIOUT_7") (pintype "bidirectional"))
      (node (ref "IC7") (pin "27") (pinfunction "PB1_27") (pintype "bidirectional"))
    )
    (net (code "12") (name "I_MOT2") (class "Default")
      (node (ref "IC4") (pin "7") (pinfunction "VIOUT_7") (pintype "bidirectional"))
      (node (ref "IC7") (pin "26") (pinfunction "PB0_26") (pintype "bidirectional"))
    )
    (net (code "13") (name "MOT1_DIR") (class "Default")
      (node (ref "IC5") (pin "1") (pinfunction "DIR_1") (pintype "input"))
      (node (ref "IC7") (pin "34") (pinfunction "PB13_34") (pintype "bidirectional"))
    )
    (net (code "14") (name "MOT1_EN") (class "Default")
      (node (ref "IC5") (pin "11") (pinfunction "DIS_11") (pintype "input"))
      (node (ref "IC7") (pin "35") (pinfunction "PB14_35") (pintype "bidirectional"))
    )
    (net (code "15") (name "MOT1_ENCODER_A") (class "Default")
      (node (ref "IC7") (pin "55") (pinfunction "PB3_55") (pintype "bidirectional"))
      (node (ref "U$14") (pin "B") (pinfunction "B_B") (pintype "bidirectional"))
    )
    (net (code "16") (name "MOT1_ENCODER_B") (class "Default")
      (node (ref "IC7") (pin "50") (pinfunction "PA15_50") (pintype "bidirectional"))
      (node (ref "U$14") (pin "A") (pinfunction "A_A") (pintype "bidirectional"))
    )
    (net (code "17") (name "MOT1_PWM") (class "Default")
      (node (ref "IC5") (pin "12") (pinfunction "PWM_12") (pintype "input"))
      (node (ref "IC7") (pin "37") (pinfunction "PC6_37") (pintype "bidirectional"))
    )
    (net (code "18") (name "MOT1_SO") (class "Default")
      (node (ref "IC5") (pin "3") (pinfunction "SO_3") (pintype "output"))
    )
    (net (code "19") (name "MOT2_DIR") (class "Default")
      (node (ref "IC6") (pin "1") (pinfunction "DIR_1") (pintype "input"))
      (node (ref "IC7") (pin "39") (pinfunction "PC8_39") (pintype "bidirectional"))
    )
    (net (code "20") (name "MOT2_EN") (class "Default")
      (node (ref "IC6") (pin "11") (pinfunction "DIS_11") (pintype "input"))
      (node (ref "IC7") (pin "36") (pinfunction "PB15_36") (pintype "bidirectional"))
    )
    (net (code "21") (name "MOT2_ENCODER_A") (class "Default")
      (node (ref "IC7") (pin "14") (pinfunction "PA0_14") (pintype "bidirectional"))
      (node (ref "U$13") (pin "B") (pinfunction "B_B") (pintype "bidirectional"))
    )
    (net (code "22") (name "MOT2_ENCODER_B") (class "Default")
      (node (ref "IC7") (pin "15") (pinfunction "PA1_15") (pintype "bidirectional"))
      (node (ref "U$13") (pin "A") (pinfunction "A_A") (pintype "bidirectional"))
    )
    (net (code "23") (name "MOT2_PWM") (class "Default")
      (node (ref "IC6") (pin "12") (pinfunction "PWM_12") (pintype "input"))
      (node (ref "IC7") (pin "38") (pinfunction "PC7_38") (pintype "bidirectional"))
    )
    (net (code "24") (name "MOT2_SO") (class "Default")
      (node (ref "IC6") (pin "3") (pinfunction "SO_3") (pintype "output"))
    )
    (net (code "25") (name "NRST") (class "Default")
      (node (ref "C19") (pin "1") (pinfunction "1_1") (pintype "passive"))
      (node (ref "IC7") (pin "7") (pinfunction "NRST_7") (pintype "bidirectional"))
      (node (ref "PROG-SWDIO") (pin "6") (pinfunction "S_6") (pintype "passive"))
      (node (ref "R8") (pin "1") (pinfunction "1_1") (pintype "passive"))
      (node (ref "S2") (pin "B1") (pinfunction "2_B1") (pintype "passive"))
      (node (ref "S2") (pin "B2") (pinfunction "2_B2") (pintype "passive"))
    )
    (net (code "26") (name "Net-(IC3-IP-_1)") (class "Default")
      (node (ref "IC3") (pin "3") (pinfunction "IP-_1_3") (pintype "bidirectional"))
      (node (ref "IC3") (pin "4") (pinfunction "IP-_2_4") (pintype "bidirectional"))
      (node (ref "IC5") (pin "4") (pinfunction "VS_4") (pintype "power_in"))
    )
    (net (code "27") (name "Net-(IC4-IP-_1)") (class "Default")
      (node (ref "IC4") (pin "3") (pinfunction "IP-_1_3") (pintype "bidirectional"))
      (node (ref "IC4") (pin "4") (pinfunction "IP-_2_4") (pintype "bidirectional"))
      (node (ref "IC6") (pin "4") (pinfunction "VS_4") (pintype "power_in"))
    )
    (net (code "28") (name "Net-(IC5-OUT1)") (class "Default")
      (node (ref "IC5") (pin "5") (pinfunction "OUT1_5") (pintype "output"))
      (node (ref "MOT1_A") (pin "1") (pinfunction "1_1") (pintype "passive"))
    )
    (net (code "29") (name "Net-(IC5-OUT2)") (class "Default")
      (node (ref "IC5") (pin "7") (pinfunction "OUT2_7") (pintype "output"))
      (node (ref "MOT1_B") (pin "1") (pinfunction "1_1") (pintype "passive"))
    )
    (net (code "30") (name "Net-(IC6-OUT1)") (class "Default")
      (node (ref "IC6") (pin "5") (pinfunction "OUT1_5") (pintype "output"))
      (node (ref "MOT2_A") (pin "1") (pinfunction "1_1") (pintype "passive"))
    )
    (net (code "31") (name "Net-(IC6-OUT2)") (class "Default")
      (node (ref "IC6") (pin "7") (pinfunction "OUT2_7") (pintype "output"))
      (node (ref "MOT2_B") (pin "1") (pinfunction "1_1") (pintype "passive"))
    )
    (net (code "32") (name "Net-(IC7-PH0-OSC_IN)") (class "Default")
      (node (ref "C8") (pin "2") (pinfunction "2_2") (pintype "passive"))
      (node (ref "IC7") (pin "5") (pinfunction "PH0-OSC_IN_5") (pintype "bidirectional"))
      (node (ref "Y1") (pin "3") (pinfunction "2_3") (pintype "passive"))
    )
    (net (code "33") (name "Net-(IC7-PH1-OSC_OUT)") (class "Default")
      (node (ref "C9") (pin "2") (pinfunction "2_2") (pintype "passive"))
      (node (ref "IC7") (pin "6") (pinfunction "PH1-OSC_OUT_6") (pintype "bidirectional"))
      (node (ref "Y1") (pin "1") (pinfunction "1_1") (pintype "passive"))
    )
    (net (code "34") (name "Net-(LED5-PadA)") (class "Default")
      (node (ref "LED5") (pin "A") (pinfunction "A_A") (pintype "passive"))
      (node (ref "R6") (pin "1") (pinfunction "1_1") (pintype "passive"))
    )
    (net (code "35") (name "Net-(T1-B)") (class "Default")
      (node (ref "R2") (pin "2") (pinfunction "2_2") (pintype "passive"))
      (node (ref "T1") (pin "1") (pinfunction "B_1") (pintype "passive"))
    )
    (net (code "36") (name "Net-(T1-E)") (class "Default")
      (node (ref "T1") (pin "2") (pinfunction "E_2") (pintype "passive"))
      (node (ref "U$7") (pin "VIN") (pinfunction "VIN_VIN") (pintype "bidirectional"))
    )
    (net (code "37") (name "Net-(T2-B)") (class "Default")
      (node (ref "R3") (pin "2") (pinfunction "2_2") (pintype "passive"))
      (node (ref "T2") (pin "1") (pinfunction "B_1") (pintype "passive"))
    )
    (net (code "38") (name "Net-(T2-E)") (class "Default")
      (node (ref "T2") (pin "2") (pinfunction "E_2") (pintype "passive"))
      (node (ref "U$8") (pin "VIN") (pinfunction "VIN_VIN") (pintype "bidirectional"))
    )
    (net (code "39") (name "Net-(T3-B)") (class "Default")
      (node (ref "R4") (pin "2") (pinfunction "2_2") (pintype "passive"))
      (node (ref "T3") (pin "1") (pinfunction "B_1") (pintype "passive"))
    )
    (net (code "40") (name "Net-(T3-E)") (class "Default")
      (node (ref "T3") (pin "2") (pinfunction "E_2") (pintype "passive"))
      (node (ref "U$9") (pin "VIN") (pinfunction "VIN_VIN") (pintype "bidirectional"))
    )
    (net (code "41") (name "Net-(T4-B)") (class "Default")
      (node (ref "R5") (pin "2") (pinfunction "2_2") (pintype "passive"))
      (node (ref "T4") (pin "1") (pinfunction "B_1") (pintype "passive"))
    )
    (net (code "42") (name "Net-(T4-E)") (class "Default")
      (node (ref "T4") (pin "2") (pinfunction "E_2") (pintype "passive"))
      (node (ref "U$10") (pin "VIN") (pinfunction "VIN_VIN") (pintype "bidirectional"))
    )
    (net (code "43") (name "Net-(T5-B)") (class "Default")
      (node (ref "R7") (pin "2") (pinfunction "2_2") (pintype "passive"))
      (node (ref "T5") (pin "1") (pinfunction "B_1") (pintype "passive"))
    )
    (net (code "44") (name "Net-(T5-E)") (class "Default")
      (node (ref "T5") (pin "2") (pinfunction "E_2") (pintype "passive"))
      (node (ref "U$11") (pin "VIN") (pinfunction "VIN_VIN") (pintype "bidirectional"))
    )
    (net (code "45") (name "RX") (class "Default")
      (node (ref "IC7") (pin "43") (pinfunction "PA10_43") (pintype "bidirectional"))
    )
    (net (code "46") (name "SCL") (class "Default")
      (node (ref "IC7") (pin "41") (pinfunction "PA8_41") (pintype "bidirectional"))
      (node (ref "R24") (pin "1") (pinfunction "1_1") (pintype "passive"))
      (node (ref "U$10") (pin "SCL") (pinfunction "SCL_SCL") (pintype "bidirectional"))
      (node (ref "U$11") (pin "SCL") (pinfunction "SCL_SCL") (pintype "bidirectional"))
      (node (ref "U$7") (pin "SCL") (pinfunction "SCL_SCL") (pintype "bidirectional"))
      (node (ref "U$8") (pin "SCL") (pinfunction "SCL_SCL") (pintype "bidirectional"))
      (node (ref "U$9") (pin "SCL") (pinfunction "SCL_SCL") (pintype "bidirectional"))
    )
    (net (code "47") (name "SDA") (class "Default")
      (node (ref "IC7") (pin "40") (pinfunction "PC9_40") (pintype "bidirectional"))
      (node (ref "R23") (pin "1") (pinfunction "1_1") (pintype "passive"))
      (node (ref "U$10") (pin "SDA") (pinfunction "SDA_SDA") (pintype "bidirectional"))
      (node (ref "U$11") (pin "SDA") (pinfunction "SDA_SDA") (pintype "bidirectional"))
      (node (ref "U$7") (pin "SDA") (pinfunction "SDA_SDA") (pintype "bidirectional"))
      (node (ref "U$8") (pin "SDA") (pinfunction "SDA_SDA") (pintype "bidirectional"))
      (node (ref "U$9") (pin "SDA") (pinfunction "SDA_SDA") (pintype "bidirectional"))
    )
    (net (code "48") (name "SWCLK") (class "Default")
      (node (ref "IC7") (pin "49") (pinfunction "PA14_49") (pintype "bidirectional"))
      (node (ref "PROG-SWDIO") (pin "5") (pinfunction "S_5") (pintype "passive"))
    )
    (net (code "49") (name "SWDIO") (class "Default")
      (node (ref "IC7") (pin "46") (pinfunction "PA13_46") (pintype "bidirectional"))
      (node (ref "PROG-SWDIO") (pin "3") (pinfunction "S_3") (pintype "passive"))
    )
    (net (code "50") (name "SWIM") (class "Default")
      (node (ref "PROG-SWDIO") (pin "4") (pinfunction "S_4") (pintype "passive"))
    )
    (net (code "51") (name "SW_1") (class "Default")
      (node (ref "IC7") (pin "8") (pinfunction "PC0_8") (pintype "bidirectional"))
      (node (ref "R25") (pin "1") (pinfunction "1_1") (pintype "passive"))
      (node (ref "S3") (pin "8") (pinfunction "8_8") (pintype "passive"))
    )
    (net (code "52") (name "SW_2") (class "Default")
      (node (ref "IC7") (pin "9") (pinfunction "PC1_9") (pintype "bidirectional"))
      (node (ref "R26") (pin "1") (pinfunction "1_1") (pintype "passive"))
      (node (ref "S3") (pin "7") (pinfunction "7_7") (pintype "passive"))
    )
    (net (code "53") (name "SW_3") (class "Default")
      (node (ref "IC7") (pin "10") (pinfunction "PC2_10") (pintype "bidirectional"))
      (node (ref "R27") (pin "1") (pinfunction "1_1") (pintype "passive"))
      (node (ref "S3") (pin "6") (pinfunction "6_6") (pintype "passive"))
    )
    (net (code "54") (name "SW_4") (class "Default")
      (node (ref "IC7") (pin "11") (pinfunction "PC3_11") (pintype "bidirectional"))
      (node (ref "R28") (pin "1") (pinfunction "1_1") (pintype "passive"))
      (node (ref "S3") (pin "5") (pinfunction "5_5") (pintype "passive"))
    )
    (net (code "55") (name "TX") (class "Default")
      (node (ref "IC7") (pin "42") (pinfunction "PA9_42") (pintype "bidirectional"))
    )
    (net (code "56") (name "V+") (class "Default")
      (node (ref "C16") (pin "1") (pinfunction "1_1") (pintype "passive"))
      (node (ref "C3") (pin "+") (pinfunction "+_+") (pintype "passive"))
      (node (ref "C32") (pin "+") (pinfunction "+_+") (pintype "passive"))
      (node (ref "C34") (pin "+") (pinfunction "+_+") (pintype "passive"))
      (node (ref "C7") (pin "+") (pinfunction "+_+") (pintype "passive"))
      (node (ref "IC3") (pin "1") (pinfunction "IP+_1_1") (pintype "bidirectional"))
      (node (ref "IC3") (pin "2") (pinfunction "IP+_2_2") (pintype "bidirectional"))
      (node (ref "IC4") (pin "1") (pinfunction "IP+_1_1") (pintype "bidirectional"))
      (node (ref "IC4") (pin "2") (pinfunction "IP+_2_2") (pintype "bidirectional"))
      (node (ref "R6") (pin "2") (pinfunction "2_2") (pintype "passive"))
      (node (ref "S1") (pin "1") (pinfunction "O_1") (pintype "passive"))
      (node (ref "U2") (pin "3") (pinfunction "IN_3") (pintype "input"))
    )
    (net (code "57") (name "VDDA") (class "Default")
      (node (ref "C21") (pin "1") (pinfunction "1_1") (pintype "passive"))
      (node (ref "IC7") (pin "13") (pinfunction "VDDA/VREF+_13") (pintype "bidirectional"))
      (node (ref "L2") (pin "2") (pinfunction "2_2") (pintype "passive"))
    )
    (net (code "58") (name "unconnected-(IC3-FILTER-Pad6)") (class "Default")
      (node (ref "IC3") (pin "6") (pinfunction "FILTER_6") (pintype "bidirectional"))
    )
    (net (code "59") (name "unconnected-(IC4-FILTER-Pad6)") (class "Default")
      (node (ref "IC4") (pin "6") (pinfunction "FILTER_6") (pintype "bidirectional"))
    )
    (net (code "60") (name "unconnected-(IC7-PA2-Pad16)") (class "Default")
      (node (ref "IC7") (pin "16") (pinfunction "PA2_16") (pintype "bidirectional"))
    )
    (net (code "61") (name "unconnected-(IC7-PA3-Pad17)") (class "Default")
      (node (ref "IC7") (pin "17") (pinfunction "PA3_17") (pintype "bidirectional"))
    )
    (net (code "62") (name "unconnected-(IC7-PA4-Pad20)") (class "Default")
      (node (ref "IC7") (pin "20") (pinfunction "PA4_20") (pintype "bidirectional"))
    )
    (net (code "63") (name "unconnected-(IC7-PA5-Pad21)") (class "Default")
      (node (ref "IC7") (pin "21") (pinfunction "PA5_21") (pintype "bidirectional"))
    )
    (net (code "64") (name "unconnected-(IC7-PA6-Pad22)") (class "Default")
      (node (ref "IC7") (pin "22") (pinfunction "PA6_22") (pintype "bidirectional"))
    )
    (net (code "65") (name "unconnected-(IC7-PA7-Pad23)") (class "Default")
      (node (ref "IC7") (pin "23") (pinfunction "PA7_23") (pintype "bidirectional"))
    )
    (net (code "66") (name "unconnected-(IC7-PA11-Pad44)") (class "Default")
      (node (ref "IC7") (pin "44") (pinfunction "PA11_44") (pintype "bidirectional"))
    )
    (net (code "67") (name "unconnected-(IC7-PA12-Pad45)") (class "Default")
      (node (ref "IC7") (pin "45") (pinfunction "PA12_45") (pintype "bidirectional"))
    )
    (net (code "68") (name "unconnected-(IC7-PB9-Pad62)") (class "Default")
      (node (ref "IC7") (pin "62") (pinfunction "PB9_62") (pintype "bidirectional"))
    )
    (net (code "69") (name "unconnected-(IC7-PB10-Pad29)") (class "Default")
      (node (ref "IC7") (pin "29") (pinfunction "PB10_29") (pintype "bidirectional"))
    )
    (net (code "70") (name "unconnected-(IC7-PB12-Pad33)") (class "Default")
      (node (ref "IC7") (pin "33") (pinfunction "PB12_33") (pintype "bidirectional"))
    )
    (net (code "71") (name "unconnected-(IC7-PC4-Pad24)") (class "Default")
      (node (ref "IC7") (pin "24") (pinfunction "PC4_24") (pintype "bidirectional"))
    )
    (net (code "72") (name "unconnected-(IC7-PC5-Pad25)") (class "Default")
      (node (ref "IC7") (pin "25") (pinfunction "PC5_25") (pintype "bidirectional"))
    )
    (net (code "73") (name "unconnected-(IC7-PC10-Pad51)") (class "Default")
      (node (ref "IC7") (pin "51") (pinfunction "PC10_51") (pintype "bidirectional"))
    )
    (net (code "74") (name "unconnected-(IC7-PC11-Pad52)") (class "Default")
      (node (ref "IC7") (pin "52") (pinfunction "PC11_52") (pintype "bidirectional"))
    )
    (net (code "75") (name "unconnected-(IC7-PC12-Pad53)") (class "Default")
      (node (ref "IC7") (pin "53") (pinfunction "PC12_53") (pintype "bidirectional"))
    )
    (net (code "76") (name "unconnected-(IC7-PC13-Pad2)") (class "Default")
      (node (ref "IC7") (pin "2") (pinfunction "PC13_2") (pintype "bidirectional"))
    )
    (net (code "77") (name "unconnected-(IC7-PC14-OSC32_IN-Pad3)") (class "Default")
      (node (ref "IC7") (pin "3") (pinfunction "PC14-OSC32_IN_3") (pintype "bidirectional"))
    )
    (net (code "78") (name "unconnected-(IC7-PC15-OSC32_OUT-Pad4)") (class "Default")
      (node (ref "IC7") (pin "4") (pinfunction "PC15-OSC32_OUT_4") (pintype "bidirectional"))
    )
    (net (code "79") (name "unconnected-(IC7-PD2-Pad54)") (class "Default")
      (node (ref "IC7") (pin "54") (pinfunction "PD2_54") (pintype "bidirectional"))
    )
    (net (code "80") (name "unconnected-(IC7-VBAT-Pad1)") (class "Default")
      (node (ref "IC7") (pin "1") (pinfunction "VBAT_1") (pintype "bidirectional"))
    )
    (net (code "81") (name "unconnected-(IC7-VCAP_1-Pad30)") (class "Default")
      (node (ref "IC7") (pin "30") (pinfunction "VCAP_1_30") (pintype "bidirectional"))
    )
    (net (code "82") (name "unconnected-(S1-S-Pad3)") (class "Default")
      (node (ref "S1") (pin "3") (pinfunction "S_3") (pintype "passive"))
    )
    (net (code "83") (name "unconnected-(U$7-Pad3VO)") (class "Default")
      (node (ref "U$7") (pin "3VO") (pinfunction "3VO_3VO") (pintype "bidirectional"))
    )
    (net (code "84") (name "unconnected-(U$7-PadINT)") (class "Default")
      (node (ref "U$7") (pin "INT") (pinfunction "INT_INT") (pintype "bidirectional"))
    )
    (net (code "85") (name "unconnected-(U$8-Pad3VO)") (class "Default")
      (node (ref "U$8") (pin "3VO") (pinfunction "3VO_3VO") (pintype "bidirectional"))
    )
    (net (code "86") (name "unconnected-(U$8-PadINT)") (class "Default")
      (node (ref "U$8") (pin "INT") (pinfunction "INT_INT") (pintype "bidirectional"))
    )
    (net (code "87") (name "unconnected-(U$9-Pad3VO)") (class "Default")
      (node (ref "U$9") (pin "3VO") (pinfunction "3VO_3VO") (pintype "bidirectional"))
    )
    (net (code "88") (name "unconnected-(U$9-PadINT)") (class "Default")
      (node (ref "U$9") (pin "INT") (pinfunction "INT_INT") (pintype "bidirectional"))
    )
    (net (code "89") (name "unconnected-(U$10-Pad3VO)") (class "Default")
      (node (ref "U$10") (pin "3VO") (pinfunction "3VO_3VO") (pintype "bidirectional"))
    )
    (net (code "90") (name "unconnected-(U$10-PadINT)") (class "Default")
      (node (ref "U$10") (pin "INT") (pinfunction "INT_INT") (pintype "bidirectional"))
    )
    (net (code "91") (name "unconnected-(U$11-Pad3VO)") (class "Default")
      (node (ref "U$11") (pin "3VO") (pinfunction "3VO_3VO") (pintype "bidirectional"))
    )
    (net (code "92") (name "unconnected-(U$11-PadINT)") (class "Default")
      (node (ref "U$11") (pin "INT") (pinfunction "INT_INT") (pintype "bidirectional"))
    )
  )
)
